# OpAmp-Inverting-3Transistor-alt.net
KiCad netlist of a schematic drawn in EAGLE
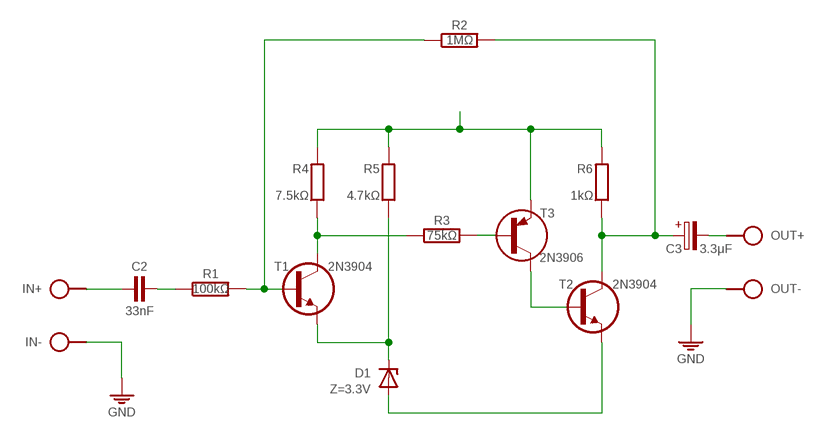
[diagram p0: schematic, sheet 1]

(export (version "E")
  (design (tool "Eeschema 10.0.6"))
  (components
    (comp (ref "C2")
      (value "33nF")
      (footprint "eagle-import:C050-020X044")
      (libsource (lib "eagle-import") (part "C050-020X044"))
    )
    (comp (ref "C3")
      (value "3.3μF")
      (footprint "eagle-import:E2.5-4_V")
      (libsource (lib "eagle-import") (part "CPOL-HE2,5-4/V"))
    )
    (comp (ref "D1")
      (value "Z=3.3V")
      (footprint "eagle-import:DO34Z5V")
      (libsource (lib "eagle-import") (part "Z-DIODE34Z5V"))
    )
    (comp (ref "IN")
      (value "SPAD+--+")
      (footprint "eagle-import:SPAD-+")
      (libsource (lib "eagle-import") (part "SPAD+--+"))
    )
    (comp (ref "OUT")
      (value "SPAD+-+-")
      (footprint "eagle-import:SPAD+-")
      (libsource (lib "eagle-import") (part "SPAD+-+-"))
    )
    (comp (ref "R1")
      (value "100kΩ")
      (footprint "eagle-import:0204_10")
      (libsource (lib "eagle-import") (part "R-H0204/10"))
    )
    (comp (ref "R2")
      (value "1MΩ")
      (footprint "eagle-import:0204_10")
      (libsource (lib "eagle-import") (part "R-H0204/10"))
    )
    (comp (ref "R3")
      (value "75kΩ")
      (footprint "eagle-import:0204_10-V")
      (libsource (lib "eagle-import") (part "R-H0204/10-V"))
    )
    (comp (ref "R4")
      (value "7.5kΩ")
      (footprint "eagle-import:0204_10-V")
      (libsource (lib "eagle-import") (part "R0204/10-V"))
    )
    (comp (ref "R5")
      (value "4.7kΩ")
      (footprint "eagle-import:0204_10-V")
      (libsource (lib "eagle-import") (part "R0204/10-V"))
    )
    (comp (ref "R6")
      (value "1kΩ")
      (footprint "eagle-import:0204_10-V")
      (libsource (lib "eagle-import") (part "R0204/10-V"))
    )
    (comp (ref "T1")
      (value "2N3904")
      (footprint "eagle-import:TO92-EBC")
      (libsource (lib "eagle-import") (part "2N3904EBC"))
    )
    (comp (ref "T2")
      (value "2N3904")
      (footprint "eagle-import:TO92-EBC")
      (libsource (lib "eagle-import") (part "2N3904EBC"))
    )
    (comp (ref "T3")
      (value "2N3906")
      (footprint "eagle-import:TO92-EBC")
      (libsource (lib "eagle-import") (part "2N3906TO92-EBC"))
    )
  )
  (nets
    (net (code "1") (name "GND") (class "Default")
      (node (ref "D1") (pin "A") (pinfunction "A_A") (pintype "passive"))
      (node (ref "IN") (pin "1") (pinfunction "P$1_1") (pintype "passive"))
      (node (ref "OUT") (pin "1") (pinfunction "P$1_1") (pintype "passive"))
      (node (ref "T2") (pin "E") (pinfunction "E_E") (pintype "passive"))
    )
    (net (code "2") (name "Net-(C2-Pad1)") (class "Default")
      (node (ref "C2") (pin "1") (pinfunction "1_1") (pintype "passive"))
      (node (ref "R1") (pin "1") (pinfunction "1_1") (pintype "passive"))
    )
    (net (code "3") (name "Net-(C3-Pad+)") (class "Default")
      (node (ref "C3") (pin "+") (pinfunction "+_+") (pintype "passive"))
      (node (ref "R2") (pin "2") (pinfunction "2_2") (pintype "passive"))
      (node (ref "R6") (pin "2") (pinfunction "2_2") (pintype "passive"))
      (node (ref "T2") (pin "C") (pinfunction "C_C") (pintype "passive"))
    )
    (net (code "4") (name "Net-(D1-PadC)") (class "Default")
      (node (ref "D1") (pin "C") (pinfunction "C_C") (pintype "passive"))
      (node (ref "R5") (pin "2") (pinfunction "2_2") (pintype "passive"))
      (node (ref "T1") (pin "E") (pinfunction "E_E") (pintype "passive"))
    )
    (net (code "5") (name "Net-(INA-P$1)") (class "Default")
      (node (ref "C2") (pin "2") (pinfunction "2_2") (pintype "passive"))
      (node (ref "IN") (pin "2") (pinfunction "P$1_2") (pintype "passive"))
    )
    (net (code "6") (name "Net-(OUTA-P$1)") (class "Default")
      (node (ref "C3") (pin "-") (pinfunction "-_-") (pintype "passive"))
      (node (ref "OUT") (pin "2") (pinfunction "P$1_2") (pintype "passive"))
    )
    (net (code "7") (name "Net-(R1-Pad2)") (class "Default")
      (node (ref "R1") (pin "2") (pinfunction "2_2") (pintype "passive"))
      (node (ref "R2") (pin "1") (pinfunction "1_1") (pintype "passive"))
      (node (ref "T1") (pin "B") (pinfunction "B_B") (pintype "passive"))
    )
    (net (code "8") (name "Net-(R3-Pad1)") (class "Default")
      (node (ref "R3") (pin "1") (pinfunction "1_1") (pintype "passive"))
      (node (ref "R4") (pin "2") (pinfunction "2_2") (pintype "passive"))
      (node (ref "T1") (pin "C") (pinfunction "C_C") (pintype "passive"))
    )
    (net (code "9") (name "Net-(R3-Pad2)") (class "Default")
      (node (ref "R3") (pin "2") (pinfunction "2_2") (pintype "passive"))
      (node (ref "T3") (pin "B") (pinfunction "B_B") (pintype "passive"))
    )
    (net (code "10") (name "Net-(R4-Pad1)") (class "Default")
      (node (ref "R4") (pin "1") (pinfunction "1_1") (pintype "passive"))
      (node (ref "R5") (pin "1") (pinfunction "1_1") (pintype "passive"))
      (node (ref "R6") (pin "1") (pinfunction "1_1") (pintype "passive"))
      (node (ref "T3") (pin "E") (pinfunction "E_E") (pintype "passive"))
    )
    (net (code "11") (name "Net-(T2-PadB)") (class "Default")
      (node (ref "T2") (pin "B") (pinfunction "B_B") (pintype "passive"))
      (node (ref "T3") (pin "C") (pinfunction "C_C") (pintype "passive"))
    )
  )
)
